# Sheet1.net
KiCad netlist of a schematic drawn in Altium Designer
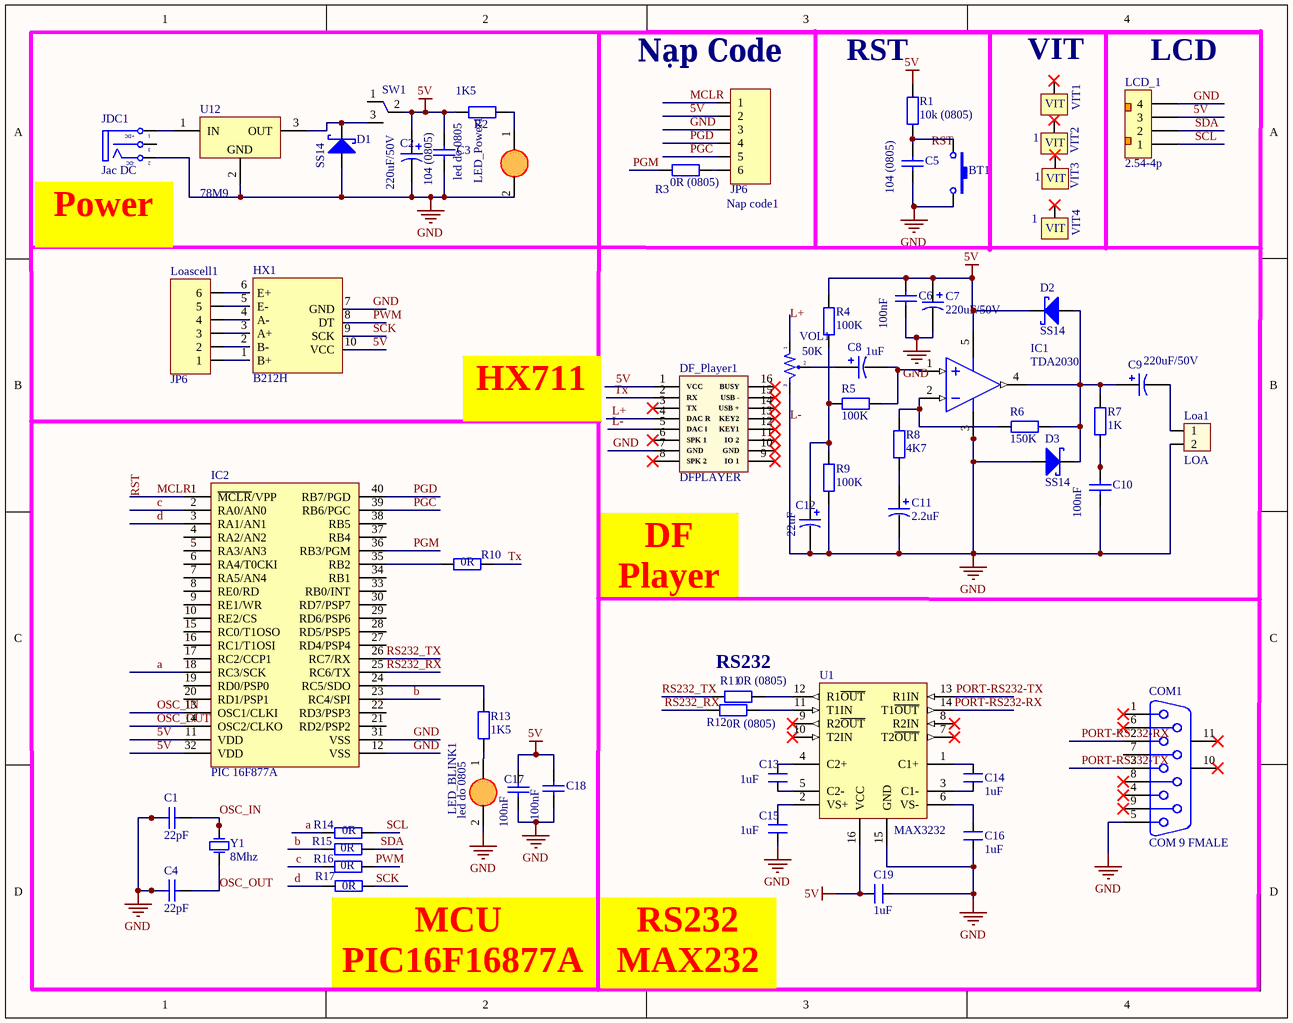
[diagram p0: Sheet1.SchDoc]

(export (version "E")
  (design (tool "Eeschema 10.0.6"))
  (components
    (comp (ref "BT1")
      (value "Nút Nhấn 2 Chân 3x6x2.5MM SMD")
      (footprint "SW2-DIP")
      (description "Dán")
      (libsource (lib "SCH Chuan") (part "Nut Nhan 2 Chan SMD"))
    )
    (comp (ref "C1")
      (value "22pF")
      (footprint "CN1.5")
      (description "Dán")
      (libsource (lib "SCH Chuan") (part "Tu 0805 104 50V 10%"))
    )
    (comp (ref "C2")
      (value "220uF/50V")
      (footprint "CP1.5/3.4")
      (description "CAP ALUM 680uF 20% 16V SMD")
      (fields (field (name "MPN") "EEE-FK1C681P") (field (name "MFR") "Panasonic"))
      (libsource (lib "NhomLib") (part "EEE-FK1C681P"))
    )
    (comp (ref "C3")
      (value "104 (0805)")
      (footprint "CN1.5")
      (description "Dán")
      (libsource (lib "SCH Chuan") (part "Tu 0805 104 50V 10%"))
    )
    (comp (ref "C4")
      (value "22pF")
      (footprint "CN1.5")
      (description "Dán")
      (libsource (lib "SCH Chuan") (part "Tu 0805 104 50V 10%"))
    )
    (comp (ref "C5")
      (value "104 (0805)")
      (footprint "CN1.5")
      (description "Dán")
      (libsource (lib "SCH Chuan") (part "Tu 0805 104 50V 10%"))
    )
    (comp (ref "C6")
      (value "100nF")
      (footprint "CN1.5")
      (description "Dán")
      (libsource (lib "SCH Chuan") (part "Tu 0805 104 50V 10%"))
    )
    (comp (ref "C7")
      (value "220uF/50V")
      (footprint "CP1.5/3.4")
      (description "CAP ALUM 680uF 20% 16V SMD")
      (fields (field (name "MPN") "EEE-FK1C681P") (field (name "MFR") "Panasonic"))
      (libsource (lib "NhomLib") (part "EEE-FK1C681P"))
    )
    (comp (ref "C8")
      (value "1uF")
      (footprint "CP1/2")
      (description "CAP ALUM 47uF 20% 50V SMD")
      (fields (field (name "MPN") "EEE-1HA470XP"))
      (libsource (lib "NhomLib") (part "EEE-1HA470XP"))
    )
    (comp (ref "C9")
      (value "220uF/50V")
      (footprint "CP1.5/3.4")
      (description "CAP ALUM 680uF 20% 16V SMD")
      (fields (field (name "MPN") "EEE-FK1C681P") (field (name "MFR") "Panasonic"))
      (libsource (lib "NhomLib") (part "EEE-FK1C681P"))
    )
    (comp (ref "C10")
      (value "100nF")
      (footprint "CN1.5")
      (description "Dán")
      (libsource (lib "SCH Chuan") (part "Tu 0805 104 50V 10%"))
    )
    (comp (ref "C11")
      (value "2.2uF")
      (footprint "CP1/2")
      (description "CAP ALUM 47uF 20% 50V SMD")
      (fields (field (name "MPN") "EEE-1HA470XP"))
      (libsource (lib "NhomLib") (part "EEE-1HA470XP"))
    )
    (comp (ref "C12")
      (value "22uF")
      (footprint "CP1/2")
      (description "CAP ALUM 47uF 20% 50V SMD")
      (fields (field (name "MPN") "EEE-1HA470XP"))
      (libsource (lib "NhomLib") (part "EEE-1HA470XP"))
    )
    (comp (ref "C13")
      (value "1uF")
      (footprint "CN1.5")
      (description "CAP CER 0.1UF 50V X7R 0805")
      (fields
        (field (name "MANUFACTURER") "AVX Corporation")
        (field (name "MANUFACTURER PART NUMBER") "08055C104KAT2A")
      )
      (libsource (lib "Tran Tuan") (part "CAP-CER/100nF/50V/X7R/0805"))
    )
    (comp (ref "C14")
      (value "1uF")
      (footprint "CN1.5")
      (description "CAP CER 0.1UF 50V X7R 0805")
      (fields
        (field (name "MANUFACTURER") "AVX Corporation")
        (field (name "MANUFACTURER PART NUMBER") "08055C104KAT2A")
      )
      (libsource (lib "Tran Tuan") (part "CAP-CER/100nF/50V/X7R/0805"))
    )
    (comp (ref "C15")
      (value "1uF")
      (footprint "CN1.5")
      (description "CAP CER 0.1UF 50V X7R 0805")
      (fields
        (field (name "MANUFACTURER") "AVX Corporation")
        (field (name "MANUFACTURER PART NUMBER") "08055C104KAT2A")
      )
      (libsource (lib "Tran Tuan") (part "CAP-CER/100nF/50V/X7R/0805"))
    )
    (comp (ref "C16")
      (value "1uF")
      (footprint "CN1.5")
      (description "CAP CER 0.1UF 50V X7R 0805")
      (fields
        (field (name "MANUFACTURER") "AVX Corporation")
        (field (name "MANUFACTURER PART NUMBER") "08055C104KAT2A")
      )
      (libsource (lib "Tran Tuan") (part "CAP-CER/100nF/50V/X7R/0805"))
    )
    (comp (ref "C17")
      (value "100nF")
      (footprint "CN1.5")
      (description "Dán")
      (libsource (lib "SCH Chuan") (part "Tu 0805 104 50V 10%"))
    )
    (comp (ref "C18")
      (value "100nF")
      (footprint "CN1.5")
      (description "Dán")
      (libsource (lib "SCH Chuan") (part "Tu 0805 104 50V 10%"))
    )
    (comp (ref "C19")
      (value "1uF")
      (footprint "CN1.5")
      (description "CAP CER 0.1UF 50V X7R 0805")
      (fields
        (field (name "MANUFACTURER") "AVX Corporation")
        (field (name "MANUFACTURER PART NUMBER") "08055C104KAT2A")
      )
      (libsource (lib "Tran Tuan") (part "CAP-CER/100nF/50V/X7R/0805"))
    )
    (comp (ref "COM1")
      (value "COM 9 FMALE")
      (footprint "DSB 9-F")
      (description "COM 9")
      (fields (field (name "PUBLISHER") "Altium Limited"))
      (libsource (lib "syhaunguyen") (part "DSB9F"))
    )
    (comp (ref "D1")
      (value "SS14")
      (footprint "DIO-1A")
      (description "Dán")
      (libsource (lib "SCH Chuan") (part "Diode SS14 ( 1N5819)"))
    )
    (comp (ref "D2")
      (value "SS14")
      (footprint "DIO-1A")
      (description "Dán")
      (libsource (lib "SCH Chuan") (part "Diode SS14 ( 1N5819)"))
    )
    (comp (ref "D3")
      (value "SS14")
      (footprint "DIO-1A")
      (description "Dán")
      (libsource (lib "SCH Chuan") (part "Diode SS14 ( 1N5819)"))
    )
    (comp (ref "DF_Player1")
      (value "DFPLAYER")
      (footprint "DFPLAYER")
      (libsource (lib "VanThoLIB") (part "DFPLAYER"))
    )
    (comp (ref "HX1")
      (value "B212H")
      (footprint "Module_HX711")
      (description "Module_HX711")
      (libsource (lib "VanThoLIB") (part "Module_HX711"))
    )
    (comp (ref "IC1")
      (value "TDA2030")
      (footprint "DIP5SL1")
      (description "14W Hi-Fi AUDIO AMPLIFIER")
      (libsource (lib "syhaunguyen") (part "TDA2030"))
    )
    (comp (ref "IC2")
      (value "PIC 16F877A")
      (footprint "DIP40/W0.6")
      (description "8K FLASH, 368B RAM, 256B EFROM")
      (fields (field (name "COPYRIGHT BY") "VanDungEvn"))
      (libsource (lib "LIBRARY") (part "PIC16F877-PU"))
    )
    (comp (ref "JDC1")
      (value "Jac DC")
      (footprint "DC-IN")
      (description "Jac DC input")
      (libsource (lib "NhomLib") (part "DCIN"))
    )
    (comp (ref "LCD_1")
      (value "2.54-4p")
      (footprint "Header Duc Thang 4p 2.54")
      (description "Cắm")
      (libsource (lib "B212H") (part "Header 2.54_4p Duc Thang"))
    )
    (comp (ref "LED_BLINK1")
      (value "led do 0805")
      (footprint "LED-5-Green")
      (description "Dán")
      (libsource (lib "SCH Chuan") (part "Led 0805 Do"))
    )
    (comp (ref "LED_Power1")
      (value "led do 0805")
      (footprint "LED-5-Green")
      (description "Dán")
      (libsource (lib "SCH Chuan") (part "Led 0805 Do"))
    )
    (comp (ref "Loa1")
      (value "LOA")
      (footprint "CON2")
      (description "Header 2.54mm Through Hole")
      (fields
        (field (name "MANUFACTURER") "TE Connectivity AMP Connectors")
        (field (name "MANUFACTURER PART NUMBER") "640456-2")
      )
      (libsource (lib "LPSON") (part "Header 2 2.54mm"))
    )
    (comp (ref "Loascell1")
      (value "JP6")
      (footprint "HDR6")
      (description "WR-PHD 2.54 mm Angled Socket Header")
      (fields
        (field (name "MANUFACTURER") "Würth Elektronik eiSos GmbH")
        (field (name "PARTNO") "613006143121")
        (field (name "CREATED BY") "Karrer Zheng")
      )
      (libsource (lib "LIBRARY") (part "JP6"))
    )
    (comp (ref "Nap code1")
      (value "JP6")
      (footprint "JP6-D1T")
      (description "WR-PHD 2.54 mm Angled Socket Header")
      (fields
        (field (name "MANUFACTURER") "Würth Elektronik eiSos GmbH")
        (field (name "PARTNO") "613006143121")
        (field (name "CREATED BY") "Karrer Zheng")
      )
      (libsource (lib "") (part "JP6_1"))
    )
    (comp (ref "R1")
      (value "10k (0805)")
      (footprint "RES-1/4W")
      (description "Dán")
      (libsource (lib "SCH Chuan") (part "Tro 0805 5% 10k"))
    )
    (comp (ref "R2")
      (value "1K5")
      (footprint "RES-1/4W")
      (description "Dán")
      (libsource (lib "SCH Chuan") (part "Tro 0805 5% 470R"))
    )
    (comp (ref "R3")
      (value "0R (0805)")
      (footprint "RES-1/4W")
      (description "Dán")
      (libsource (lib "SCH Chuan") (part "Tro 0805 5% 470R"))
    )
    (comp (ref "R4")
      (value "100K")
      (footprint "RES-1/4W")
      (description "Dán")
      (libsource (lib "SCH Chuan") (part "Tro 0805 5% 10k"))
    )
    (comp (ref "R5")
      (value "100K")
      (footprint "RES-1/4W")
      (description "Dán")
      (libsource (lib "SCH Chuan") (part "Tro 0805 5% 10k"))
    )
    (comp (ref "R6")
      (value "150K")
      (footprint "RES-1/4W")
      (description "Dán")
      (libsource (lib "SCH Chuan") (part "Tro 0805 5% 10k"))
    )
    (comp (ref "R7")
      (value "1K")
      (footprint "RES-1/4W")
      (description "Dán")
      (libsource (lib "SCH Chuan") (part "Tro 0805 5% 10k"))
    )
    (comp (ref "R8")
      (value "4K7")
      (footprint "RES-1/4W")
      (description "Dán")
      (libsource (lib "SCH Chuan") (part "Tro 0805 5% 10k"))
    )
    (comp (ref "R9")
      (value "100K")
      (footprint "RES-1/4W")
      (description "Dán")
      (libsource (lib "SCH Chuan") (part "Tro 0805 5% 10k"))
    )
    (comp (ref "R10")
      (value "0R")
      (footprint "RES-1/4W")
      (description "Dán")
      (libsource (lib "SCH Chuan") (part "Tro 0805 5% 470R"))
    )
    (comp (ref "R11")
      (value "0R (0805)")
      (footprint "RES-1/4W")
      (description "Dán")
      (libsource (lib "SCH Chuan") (part "Tro 0805 5% 470R"))
    )
    (comp (ref "R12")
      (value "0R (0805)")
      (footprint "RES-1/4W")
      (description "Dán")
      (libsource (lib "SCH Chuan") (part "Tro 0805 5% 470R"))
    )
    (comp (ref "R13")
      (value "1K5")
      (footprint "RES-1/4W")
      (description "Dán")
      (libsource (lib "SCH Chuan") (part "Tro 0805 5% 470R"))
    )
    (comp (ref "R14")
      (value "0R")
      (footprint "RES-1/4W")
      (description "Dán")
      (libsource (lib "SCH Chuan") (part "Tro 0805 5% 470R"))
    )
    (comp (ref "R15")
      (value "0R")
      (footprint "RES-1/4W")
      (description "Dán")
      (libsource (lib "SCH Chuan") (part "Tro 0805 5% 470R"))
    )
    (comp (ref "R16")
      (value "0R")
      (footprint "RES-1/4W")
      (description "Dán")
      (libsource (lib "SCH Chuan") (part "Tro 0805 5% 470R"))
    )
    (comp (ref "R17")
      (value "0R")
      (footprint "RES-1/4W")
      (description "Dán")
      (libsource (lib "SCH Chuan") (part "Tro 0805 5% 470R"))
    )
    (comp (ref "SW1") (value "Switch") (footprint "JP3-C1T") (libsource (lib "VanThoLIB") (part "Switch")))
    (comp (ref "U1")
      (value "MAX3232")
      (footprint "DIP16")
      (description "RS232 LEVEL SHIFTER")
      (fields
        (field (name "MANUFACTURER PART NUMBER") "MAX232DR")
        (field (name "MANUFACTURER") "Texas Instruments")
      )
      (libsource (lib "LIBRARY") (part "MAX232"))
    )
    (comp (ref "U12")
      (value "78M9")
      (footprint "HDR1x3 BIG")
      (description "Dán")
      (libsource (lib "NhomLib") (part "7809"))
    )
    (comp (ref "VIT1")
      (value "1")
      (footprint "VIT")
      (description "Oc Vit")
      (libsource (lib "syhaunguyen") (part "VIT"))
    )
    (comp (ref "VIT2")
      (value "1")
      (footprint "VIT")
      (description "Oc Vit")
      (libsource (lib "syhaunguyen") (part "VIT"))
    )
    (comp (ref "VIT3")
      (value "1")
      (footprint "VIT")
      (description "Oc Vit")
      (libsource (lib "syhaunguyen") (part "VIT"))
    )
    (comp (ref "VIT4")
      (value "1")
      (footprint "VIT")
      (description "Oc Vit")
      (libsource (lib "syhaunguyen") (part "VIT"))
    )
    (comp (ref "VOL1")
      (value "50K")
      (footprint "VOL-D")
      (description "Var Resistor")
      (libsource (lib "syhaunguyen") (part "VOL-S"))
    )
    (comp (ref "Y1")
      (value "8Mhz")
      (footprint "THACH ANH CAM")
      (description "Dán")
      (libsource (lib "B212H") (part "Thach Anh 7.3728Mhz 49s SMD"))
    )
  )
  (nets
    (net (code "1") (name "/L+") (class "Default")
      (node (ref "DF_Player1") (pin "4") (pinfunction "DAC_R_4") (pintype "passive"))
      (node (ref "VOL1") (pin "1") (pinfunction "1_1") (pintype "passive"))
    )
    (net (code "2") (name "/MCLR") (class "Default")
      (node (ref "IC2") (pin "1") (pinfunction "~{MCLR}/VPP_1") (pintype "passive"))
      (node (ref "Nap code1") (pin "1") (pinfunction "1_1") (pintype "passive"))
    )
    (net (code "3") (name "/OSC_IN") (class "Default")
      (node (ref "C1") (pin "1") (pinfunction "1_1") (pintype "passive"))
      (node (ref "IC2") (pin "13") (pinfunction "OSC1/CLKI_13") (pintype "passive"))
      (node (ref "Y1") (pin "1") (pinfunction "OSC1_1") (pintype "passive"))
    )
    (net (code "4") (name "/OSC_OUT") (class "Default")
      (node (ref "C4") (pin "1") (pinfunction "1_1") (pintype "passive"))
      (node (ref "IC2") (pin "14") (pinfunction "OSC2/CLKO_14") (pintype "passive"))
      (node (ref "Y1") (pin "2") (pinfunction "OSC2_2") (pintype "passive"))
    )
    (net (code "5") (name "/PGC") (class "Default")
      (node (ref "IC2") (pin "39") (pinfunction "RB6/PGC_39") (pintype "passive"))
      (node (ref "Nap code1") (pin "5") (pinfunction "5_5") (pintype "passive"))
    )
    (net (code "6") (name "/PGD") (class "Default")
      (node (ref "IC2") (pin "40") (pinfunction "RB7/PGD_40") (pintype "passive"))
      (node (ref "Nap code1") (pin "4") (pinfunction "4_4") (pintype "passive"))
    )
    (net (code "7") (name "/PGM") (class "Default")
      (node (ref "IC2") (pin "36") (pinfunction "RB3/PGM_36") (pintype "passive"))
      (node (ref "R3") (pin "1") (pinfunction "1_1") (pintype "passive"))
    )
    (net (code "8") (name "/PORT-RS232-RX") (class "Default")
      (node (ref "COM1") (pin "2") (pinfunction "2_2") (pintype "passive"))
      (node (ref "U1") (pin "14") (pinfunction "T1~{OUT}_14") (pintype "output"))
    )
    (net (code "9") (name "/PORT-RS232-TX") (class "Default")
      (node (ref "COM1") (pin "3") (pinfunction "3_3") (pintype "passive"))
      (node (ref "U1") (pin "13") (pinfunction "R1IN_13") (pintype "input"))
    )
    (net (code "10") (name "/PWM") (class "Default")
      (node (ref "HX1") (pin "8") (pinfunction "DT_8") (pintype "input"))
      (node (ref "R16") (pin "2") (pinfunction "2_2") (pintype "passive"))
    )
    (net (code "11") (name "/RS232_RX") (class "Default")
      (node (ref "IC2") (pin "25") (pinfunction "RC6/TX_25") (pintype "passive"))
      (node (ref "R12") (pin "1") (pinfunction "1_1") (pintype "passive"))
    )
    (net (code "12") (name "/RS232_TX") (class "Default")
      (node (ref "IC2") (pin "26") (pinfunction "RC7/RX_26") (pintype "passive"))
      (node (ref "R11") (pin "1") (pinfunction "1_1") (pintype "passive"))
    )
    (net (code "13") (name "/SCK") (class "Default")
      (node (ref "HX1") (pin "9") (pinfunction "SCK_9") (pintype "input"))
      (node (ref "R17") (pin "1") (pinfunction "1_1") (pintype "passive"))
    )
    (net (code "14") (name "/SCL") (class "Default")
      (node (ref "LCD_1") (pin "1") (pinfunction "1_1") (pintype "passive"))
      (node (ref "R14") (pin "2") (pinfunction "2_2") (pintype "passive"))
    )
    (net (code "15") (name "/SDA") (class "Default")
      (node (ref "LCD_1") (pin "2") (pinfunction "2_2") (pintype "passive"))
      (node (ref "R15") (pin "2") (pinfunction "2_2") (pintype "passive"))
    )
    (net (code "16") (name "/Tx") (class "Default")
      (node (ref "DF_Player1") (pin "2") (pinfunction "RX_2") (pintype "passive"))
      (node (ref "R10") (pin "2") (pinfunction "2_2") (pintype "passive"))
    )
    (net (code "17") (name "/a") (class "Default")
      (node (ref "IC2") (pin "18") (pinfunction "RC3/SCK_18") (pintype "passive"))
      (node (ref "R14") (pin "1") (pinfunction "1_1") (pintype "passive"))
    )
    (net (code "18") (name "/b") (class "Default")
      (node (ref "IC2") (pin "23") (pinfunction "RC4/SPI_23") (pintype "passive"))
      (node (ref "R15") (pin "1") (pinfunction "1_1") (pintype "passive"))
    )
    (net (code "19") (name "/c") (class "Default")
      (node (ref "IC2") (pin "2") (pinfunction "RA0/AN0_2") (pintype "passive"))
      (node (ref "R16") (pin "1") (pinfunction "1_1") (pintype "passive"))
    )
    (net (code "20") (name "/d") (class "Default")
      (node (ref "IC2") (pin "3") (pinfunction "RA1/AN1_3") (pintype "passive"))
      (node (ref "R17") (pin "2") (pinfunction "2_2") (pintype "passive"))
    )
    (net (code "21") (name "5V") (class "Default")
      (node (ref "C17") (pin "1") (pinfunction "1_1") (pintype "passive"))
      (node (ref "C18") (pin "1") (pinfunction "1_1") (pintype "passive"))
      (node (ref "C19") (pin "1") (pinfunction "1_1") (pintype "passive"))
      (node (ref "C2") (pin "1") (pinfunction "1_1") (pintype "passive"))
      (node (ref "C3") (pin "1") (pinfunction "1_1") (pintype "passive"))
      (node (ref "C6") (pin "1") (pinfunction "1_1") (pintype "passive"))
      (node (ref "C7") (pin "1") (pinfunction "1_1") (pintype "passive"))
      (node (ref "D2") (pin "2") (pinfunction "K_2") (pintype "passive"))
      (node (ref "DF_Player1") (pin "1") (pinfunction "VCC_1") (pintype "power_in"))
      (node (ref "HX1") (pin "10") (pinfunction "VCC_10") (pintype "input"))
      (node (ref "IC1") (pin "5") (pinfunction "V+_5") (pintype "power_in"))
      (node (ref "IC2") (pin "11") (pinfunction "VDD_11") (pintype "passive"))
      (node (ref "IC2") (pin "32") (pinfunction "VDD_32") (pintype "passive"))
      (node (ref "LCD_1") (pin "3") (pinfunction "3_3") (pintype "passive"))
      (node (ref "Nap code1") (pin "2") (pinfunction "2_2") (pintype "passive"))
      (node (ref "R1") (pin "2") (pinfunction "2_2") (pintype "passive"))
      (node (ref "R2") (pin "1") (pinfunction "1_1") (pintype "passive"))
      (node (ref "R4") (pin "1") (pinfunction "1_1") (pintype "passive"))
      (node (ref "SW1") (pin "2") (pinfunction "1_2") (pintype "passive"))
      (node (ref "U1") (pin "16") (pinfunction "VCC_16") (pintype "power_in"))
    )
    (net (code "22") (name "GND") (class "Default")
      (node (ref "BT1") (pin "2") (pinfunction "2_2") (pintype "passive"))
      (node (ref "C1") (pin "2") (pinfunction "2_2") (pintype "passive"))
      (node (ref "C10") (pin "2") (pinfunction "2_2") (pintype "passive"))
      (node (ref "C11") (pin "2") (pinfunction "2_2") (pintype "passive"))
      (node (ref "C12") (pin "2") (pinfunction "2_2") (pintype "passive"))
      (node (ref "C15") (pin "2") (pinfunction "2_2") (pintype "passive"))
      (node (ref "C16") (pin "2") (pinfunction "2_2") (pintype "passive"))
      (node (ref "C17") (pin "2") (pinfunction "2_2") (pintype "passive"))
      (node (ref "C18") (pin "2") (pinfunction "2_2") (pintype "passive"))
      (node (ref "C19") (pin "2") (pinfunction "2_2") (pintype "passive"))
      (node (ref "C2") (pin "2") (pinfunction "2_2") (pintype "passive"))
      (node (ref "C3") (pin "2") (pinfunction "2_2") (pintype "passive"))
      (node (ref "C4") (pin "2") (pinfunction "2_2") (pintype "passive"))
      (node (ref "C5") (pin "2") (pinfunction "2_2") (pintype "passive"))
      (node (ref "C6") (pin "2") (pinfunction "2_2") (pintype "passive"))
      (node (ref "C7") (pin "2") (pinfunction "2_2") (pintype "passive"))
      (node (ref "COM1") (pin "5") (pinfunction "5_5") (pintype "passive"))
      (node (ref "D1") (pin "1") (pinfunction "A_1") (pintype "passive"))
      (node (ref "D3") (pin "1") (pinfunction "A_1") (pintype "passive"))
      (node (ref "DF_Player1") (pin "5") (pinfunction "DAC_l_5") (pintype "passive"))
      (node (ref "DF_Player1") (pin "7") (pinfunction "GND_7") (pintype "power_in"))
      (node (ref "HX1") (pin "7") (pinfunction "GND_7") (pintype "input"))
      (node (ref "IC1") (pin "3") (pinfunction "V-_3") (pintype "power_in"))
      (node (ref "IC2") (pin "12") (pinfunction "VSS_12") (pintype "passive"))
      (node (ref "IC2") (pin "31") (pinfunction "VSS_31") (pintype "passive"))
      (node (ref "JDC1") (pin "2") (pinfunction "TN_2") (pintype "passive"))
      (node (ref "LCD_1") (pin "4") (pinfunction "4_4") (pintype "passive"))
      (node (ref "LED_BLINK1") (pin "2") (pinfunction "K_2") (pintype "passive"))
      (node (ref "LED_Power1") (pin "2") (pinfunction "K_2") (pintype "passive"))
      (node (ref "Loa1") (pin "2") (pinfunction "2_2") (pintype "passive"))
      (node (ref "Nap code1") (pin "3") (pinfunction "3_3") (pintype "passive"))
      (node (ref "R9") (pin "2") (pinfunction "2_2") (pintype "passive"))
      (node (ref "U1") (pin "15") (pinfunction "GND_15") (pintype "power_in"))
      (node (ref "U12") (pin "2") (pinfunction "GND_2") (pintype "power_in"))
      (node (ref "VOL1") (pin "3") (pinfunction "3_3") (pintype "passive"))
    )
    (net (code "23") (name "Net-(BT1-Pad1)") (class "Default")
      (node (ref "BT1") (pin "1") (pinfunction "1_1") (pintype "passive"))
      (node (ref "C5") (pin "1") (pinfunction "1_1") (pintype "passive"))
      (node (ref "R1") (pin "1") (pinfunction "1_1") (pintype "passive"))
    )
    (net (code "24") (name "Net-(C8-Pad1)") (class "Default")
      (node (ref "C8") (pin "1") (pinfunction "1_1") (pintype "passive"))
      (node (ref "VOL1") (pin "2") (pinfunction "2_2") (pintype "passive"))
    )
    (net (code "25") (name "Net-(C9-Pad2)") (class "Default")
      (node (ref "C9") (pin "2") (pinfunction "2_2") (pintype "passive"))
      (node (ref "Loa1") (pin "1") (pinfunction "1_1") (pintype "passive"))
    )
    (net (code "26") (name "Net-(C10-Pad1)") (class "Default")
      (node (ref "C10") (pin "1") (pinfunction "1_1") (pintype "passive"))
      (node (ref "R7") (pin "2") (pinfunction "2_2") (pintype "passive"))
    )
    (net (code "27") (name "Net-(C11-Pad1)") (class "Default")
      (node (ref "C11") (pin "1") (pinfunction "1_1") (pintype "passive"))
      (node (ref "R8") (pin "2") (pinfunction "2_2") (pintype "passive"))
    )
    (net (code "28") (name "Net-(C12-Pad1)") (class "Default")
      (node (ref "C12") (pin "1") (pinfunction "1_1") (pintype "passive"))
      (node (ref "R4") (pin "2") (pinfunction "2_2") (pintype "passive"))
      (node (ref "R5") (pin "2") (pinfunction "2_2") (pintype "passive"))
      (node (ref "R9") (pin "1") (pinfunction "1_1") (pintype "passive"))
    )
    (net (code "29") (name "Net-(D1-K)") (class "Default")
      (node (ref "D1") (pin "2") (pinfunction "K_2") (pintype "passive"))
      (node (ref "SW1") (pin "3") (pinfunction "1_3") (pintype "passive"))
      (node (ref "U12") (pin "3") (pinfunction "OUT_3") (pintype "power_in"))
    )
    (net (code "30") (name "Net-(D2-A)") (class "Default")
      (node (ref "C9") (pin "1") (pinfunction "1_1") (pintype "passive"))
      (node (ref "D2") (pin "1") (pinfunction "A_1") (pintype "passive"))
      (node (ref "D3") (pin "2") (pinfunction "K_2") (pintype "passive"))
      (node (ref "IC1") (pin "4") (pinfunction "OUT_4") (pintype "output"))
      (node (ref "R6") (pin "1") (pinfunction "1_1") (pintype "passive"))
      (node (ref "R7") (pin "1") (pinfunction "1_1") (pintype "passive"))
    )
    (net (code "31") (name "Net-(HX1-A+)") (class "Default")
      (node (ref "HX1") (pin "3") (pinfunction "A+_3") (pintype "input"))
      (node (ref "Loascell1") (pin "3") (pinfunction "3_3") (pintype "passive"))
    )
    (net (code "32") (name "Net-(HX1-A-)") (class "Default")
      (node (ref "HX1") (pin "4") (pinfunction "A-_4") (pintype "input"))
      (node (ref "Loascell1") (pin "4") (pinfunction "4_4") (pintype "passive"))
    )
    (net (code "33") (name "Net-(HX1-B+)") (class "Default")
      (node (ref "HX1") (pin "1") (pinfunction "B+_1") (pintype "input"))
      (node (ref "Loascell1") (pin "1") (pinfunction "1_1") (pintype "passive"))
    )
    (net (code "34") (name "Net-(HX1-B-)") (class "Default")
      (node (ref "HX1") (pin "2") (pinfunction "B-_2") (pintype "input"))
      (node (ref "Loascell1") (pin "2") (pinfunction "2_2") (pintype "passive"))
    )
    (net (code "35") (name "Net-(HX1-E+)") (class "Default")
      (node (ref "HX1") (pin "6") (pinfunction "E+_6") (pintype "input"))
      (node (ref "Loascell1") (pin "6") (pinfunction "6_6") (pintype "passive"))
    )
    (net (code "36") (name "Net-(HX1-E-)") (class "Default")
      (node (ref "HX1") (pin "5") (pinfunction "E-_5") (pintype "input"))
      (node (ref "Loascell1") (pin "5") (pinfunction "5_5") (pintype "passive"))
    )
    (net (code "37") (name "Net-(IC1-IN+)") (class "Default")
      (node (ref "C8") (pin "2") (pinfunction "2_2") (pintype "passive"))
      (node (ref "IC1") (pin "1") (pinfunction "IN+_1") (pintype "input"))
      (node (ref "R5") (pin "1") (pinfunction "1_1") (pintype "passive"))
    )
    (net (code "38") (name "Net-(IC1-IN-)") (class "Default")
      (node (ref "IC1") (pin "2") (pinfunction "IN-_2") (pintype "input"))
      (node (ref "R6") (pin "2") (pinfunction "2_2") (pintype "passive"))
      (node (ref "R8") (pin "1") (pinfunction "1_1") (pintype "passive"))
    )
    (net (code "39") (name "Net-(IC2-RB2)") (class "Default")
      (node (ref "IC2") (pin "35") (pinfunction "RB2_35") (pintype "passive"))
      (node (ref "R10") (pin "1") (pinfunction "1_1") (pintype "passive"))
    )
    (net (code "40") (name "Net-(IC2-RC5{slash}SDO)") (class "Default")
      (node (ref "IC2") (pin "24") (pinfunction "RC5/SDO_24") (pintype "passive"))
      (node (ref "R13") (pin "2") (pinfunction "2_2") (pintype "passive"))
    )
    (net (code "41") (name "Net-(JDC1-T)") (class "Default")
      (node (ref "JDC1") (pin "1") (pinfunction "T_1") (pintype "passive"))
      (node (ref "U12") (pin "1") (pinfunction "IN_1") (pintype "power_in"))
    )
    (net (code "42") (name "Net-(LED_BLINK1-A)") (class "Default")
      (node (ref "LED_BLINK1") (pin "1") (pinfunction "A_1") (pintype "passive"))
      (node (ref "R13") (pin "1") (pinfunction "1_1") (pintype "passive"))
    )
    (net (code "43") (name "Net-(LED_Power1-A)") (class "Default")
      (node (ref "LED_Power1") (pin "1") (pinfunction "A_1") (pintype "passive"))
      (node (ref "R2") (pin "2") (pinfunction "2_2") (pintype "passive"))
    )
    (net (code "44") (name "Net-(Nap code1-Pad6)") (class "Default")
      (node (ref "Nap code1") (pin "6") (pinfunction "6_6") (pintype "passive"))
      (node (ref "R3") (pin "2") (pinfunction "2_2") (pintype "passive"))
    )
    (net (code "45") (name "Net-(U1-C1+)") (class "Default")
      (node (ref "C14") (pin "1") (pinfunction "1_1") (pintype "passive"))
      (node (ref "U1") (pin "1") (pinfunction "C1+_1") (pintype "passive"))
    )
    (net (code "46") (name "Net-(U1-C1-)") (class "Default")
      (node (ref "C14") (pin "2") (pinfunction "2_2") (pintype "passive"))
      (node (ref "U1") (pin "3") (pinfunction "C1-_3") (pintype "passive"))
    )
    (net (code "47") (name "Net-(U1-C2+)") (class "Default")
      (node (ref "C13") (pin "1") (pinfunction "1_1") (pintype "passive"))
      (node (ref "U1") (pin "4") (pinfunction "C2+_4") (pintype "passive"))
    )
    (net (code "48") (name "Net-(U1-C2-)") (class "Default")
      (node (ref "C13") (pin "2") (pinfunction "2_2") (pintype "passive"))
      (node (ref "U1") (pin "5") (pinfunction "C2-_5") (pintype "passive"))
    )
    (net (code "49") (name "Net-(U1-R1~{OUT})") (class "Default")
      (node (ref "R11") (pin "2") (pinfunction "2_2") (pintype "passive"))
      (node (ref "U1") (pin "12") (pinfunction "R1~{OUT}_12") (pintype "output"))
    )
    (net (code "50") (name "Net-(U1-T1IN)") (class "Default")
      (node (ref "R12") (pin "2") (pinfunction "2_2") (pintype "passive"))
      (node (ref "U1") (pin "11") (pinfunction "T1IN_11") (pintype "input"))
    )
    (net (code "51") (name "Net-(U1-VS+)") (class "Default")
      (node (ref "C15") (pin "1") (pinfunction "1_1") (pintype "passive"))
      (node (ref "U1") (pin "2") (pinfunction "VS+_2") (pintype "power_in"))
    )
    (net (code "52") (name "Net-(U1-VS-)") (class "Default")
      (node (ref "C16") (pin "1") (pinfunction "1_1") (pintype "passive"))
      (node (ref "U1") (pin "6") (pinfunction "VS-_6") (pintype "power_in"))
    )
    (net (code "53") (name "unconnected-(COM1-MH1-Pad10)") (class "Default")
      (node (ref "COM1") (pin "10") (pinfunction "MH1_10") (pintype "passive+no_connect"))
    )
    (net (code "54") (name "unconnected-(COM1-MH2-Pad11)") (class "Default")
      (node (ref "COM1") (pin "11") (pinfunction "MH2_11") (pintype "passive+no_connect"))
    )
    (net (code "55") (name "unconnected-(COM1-Pad1)") (class "Default")
      (node (ref "COM1") (pin "1") (pinfunction "1_1") (pintype "passive+no_connect"))
    )
    (net (code "56") (name "unconnected-(COM1-Pad4)") (class "Default")
      (node (ref "COM1") (pin "4") (pinfunction "4_4") (pintype "passive+no_connect"))
    )
    (net (code "57") (name "unconnected-(COM1-Pad6)") (class "Default")
      (node (ref "COM1") (pin "6") (pinfunction "6_6") (pintype "passive+no_connect"))
    )
    (net (code "58") (name "unconnected-(COM1-Pad7)") (class "Default")
      (node (ref "COM1") (pin "7") (pinfunction "7_7") (pintype "passive"))
    )
    (net (code "59") (name "unconnected-(COM1-Pad8)") (class "Default")
      (node (ref "COM1") (pin "8") (pinfunction "8_8") (pintype "passive+no_connect"))
    )
    (net (code "60") (name "unconnected-(COM1-Pad9)") (class "Default")
      (node (ref "COM1") (pin "9") (pinfunction "9_9") (pintype "passive+no_connect"))
    )
    (net (code "61") (name "unconnected-(DF_Player1-BUSY-Pad16)") (class "Default")
      (node (ref "DF_Player1") (pin "16") (pinfunction "BUSY_16") (pintype "power_in+no_connect"))
    )
    (net (code "62") (name "unconnected-(DF_Player1-GND-Pad10)") (class "Default")
      (node (ref "DF_Player1") (pin "10") (pinfunction "GND_10") (pintype "power_in+no_connect"))
    )
    (net (code "63") (name "unconnected-(DF_Player1-IO_1-Pad9)") (class "Default")
      (node (ref "DF_Player1") (pin "9") (pinfunction "IO_1_9") (pintype "passive+no_connect"))
    )
    (net (code "64") (name "unconnected-(DF_Player1-IO_2-Pad11)") (class "Default")
      (node (ref "DF_Player1") (pin "11") (pinfunction "IO_2_11") (pintype "passive+no_connect"))
    )
    (net (code "65") (name "unconnected-(DF_Player1-KEY1-Pad12)") (class "Default")
      (node (ref "DF_Player1") (pin "12") (pinfunction "KEY1_12") (pintype "passive+no_connect"))
    )
    (net (code "66") (name "unconnected-(DF_Player1-KEY2-Pad13)") (class "Default")
      (node (ref "DF_Player1") (pin "13") (pinfunction "KEY2_13") (pintype "passive+no_connect"))
    )
    (net (code "67") (name "unconnected-(DF_Player1-SPK_1-Pad6)") (class "Default")
      (node (ref "DF_Player1") (pin "6") (pinfunction "SPK_1_6") (pintype "passive+no_connect"))
    )
    (net (code "68") (name "unconnected-(DF_Player1-SPK_2-Pad8)") (class "Default")
      (node (ref "DF_Player1") (pin "8") (pinfunction "SPK_2_8") (pintype "passive+no_connect"))
    )
    (net (code "69") (name "unconnected-(DF_Player1-TX-Pad3)") (class "Default")
      (node (ref "DF_Player1") (pin "3") (pinfunction "TX_3") (pintype "passive+no_connect"))
    )
    (net (code "70") (name "unconnected-(DF_Player1-USB_+-Pad14)") (class "Default")
      (node (ref "DF_Player1") (pin "14") (pinfunction "USB_+_14") (pintype "passive+no_connect"))
    )
    (net (code "71") (name "unconnected-(DF_Player1-USB_--Pad15)") (class "Default")
      (node (ref "DF_Player1") (pin "15") (pinfunction "USB_-_15") (pintype "passive+no_connect"))
    )
    (net (code "72") (name "unconnected-(IC2-RA2{slash}AN2-Pad4)") (class "Default")
      (node (ref "IC2") (pin "4") (pinfunction "RA2/AN2_4") (pintype "passive"))
    )
    (net (code "73") (name "unconnected-(IC2-RA3{slash}AN3-Pad5)") (class "Default")
      (node (ref "IC2") (pin "5") (pinfunction "RA3/AN3_5") (pintype "passive"))
    )
    (net (code "74") (name "unconnected-(IC2-RA4{slash}T0CKI-Pad6)") (class "Default")
      (node (ref "IC2") (pin "6") (pinfunction "RA4/T0CKI_6") (pintype "passive"))
    )
    (net (code "75") (name "unconnected-(IC2-RA5{slash}AN4-Pad7)") (class "Default")
      (node (ref "IC2") (pin "7") (pinfunction "RA5/AN4_7") (pintype "passive"))
    )
    (net (code "76") (name "unconnected-(IC2-RB0{slash}INT-Pad33)") (class "Default")
      (node (ref "IC2") (pin "33") (pinfunction "RB0/INT_33") (pintype "passive"))
    )
    (net (code "77") (name "unconnected-(IC2-RB1-Pad34)") (class "Default")
      (node (ref "IC2") (pin "34") (pinfunction "RB1_34") (pintype "passive"))
    )
    (net (code "78") (name "unconnected-(IC2-RB4-Pad37)") (class "Default")
      (node (ref "IC2") (pin "37") (pinfunction "RB4_37") (pintype "passive"))
    )
    (net (code "79") (name "unconnected-(IC2-RB5-Pad38)") (class "Default")
      (node (ref "IC2") (pin "38") (pinfunction "RB5_38") (pintype "passive"))
    )
    (net (code "80") (name "unconnected-(IC2-RC0{slash}T1OSO-Pad15)") (class "Default")
      (node (ref "IC2") (pin "15") (pinfunction "RC0/T1OSO_15") (pintype "passive"))
    )
    (net (code "81") (name "unconnected-(IC2-RC1{slash}T1OSI-Pad16)") (class "Default")
      (node (ref "IC2") (pin "16") (pinfunction "RC1/T1OSI_16") (pintype "passive"))
    )
    (net (code "82") (name "unconnected-(IC2-RC2{slash}CCP1-Pad17)") (class "Default")
      (node (ref "IC2") (pin "17") (pinfunction "RC2/CCP1_17") (pintype "passive"))
    )
    (net (code "83") (name "unconnected-(IC2-RD0{slash}PSP0-Pad19)") (class "Default")
      (node (ref "IC2") (pin "19") (pinfunction "RD0/PSP0_19") (pintype "passive"))
    )
    (net (code "84") (name "unconnected-(IC2-RD1{slash}PSP1-Pad20)") (class "Default")
      (node (ref "IC2") (pin "20") (pinfunction "RD1/PSP1_20") (pintype "passive"))
    )
    (net (code "85") (name "unconnected-(IC2-RD2{slash}PSP2-Pad21)") (class "Default")
      (node (ref "IC2") (pin "21") (pinfunction "RD2/PSP2_21") (pintype "passive"))
    )
    (net (code "86") (name "unconnected-(IC2-RD3{slash}PSP3-Pad22)") (class "Default")
      (node (ref "IC2") (pin "22") (pinfunction "RD3/PSP3_22") (pintype "passive"))
    )
    (net (code "87") (name "unconnected-(IC2-RD4{slash}PSP4-Pad27)") (class "Default")
      (node (ref "IC2") (pin "27") (pinfunction "RD4/PSP4_27") (pintype "passive"))
    )
    (net (code "88") (name "unconnected-(IC2-RD5{slash}PSP5-Pad28)") (class "Default")
      (node (ref "IC2") (pin "28") (pinfunction "RD5/PSP5_28") (pintype "passive"))
    )
    (net (code "89") (name "unconnected-(IC2-RD6{slash}PSP6-Pad29)") (class "Default")
      (node (ref "IC2") (pin "29") (pinfunction "RD6/PSP6_29") (pintype "passive"))
    )
    (net (code "90") (name "unconnected-(IC2-RD7{slash}PSP7-Pad30)") (class "Default")
      (node (ref "IC2") (pin "30") (pinfunction "RD7/PSP7_30") (pintype "passive"))
    )
    (net (code "91") (name "unconnected-(IC2-RE0{slash}RD-Pad8)") (class "Default")
      (node (ref "IC2") (pin "8") (pinfunction "RE0/RD_8") (pintype "passive"))
    )
    (net (code "92") (name "unconnected-(IC2-RE1{slash}WR-Pad9)") (class "Default")
      (node (ref "IC2") (pin "9") (pinfunction "RE1/WR_9") (pintype "passive"))
    )
    (net (code "93") (name "unconnected-(IC2-RE2{slash}CS-Pad10)") (class "Default")
      (node (ref "IC2") (pin "10") (pinfunction "RE2/CS_10") (pintype "passive"))
    )
    (net (code "94") (name "unconnected-(JDC1-S-Pad3)") (class "Default")
      (node (ref "JDC1") (pin "3") (pinfunction "S_3") (pintype "power_in"))
    )
    (net (code "95") (name "unconnected-(SW1-Pad1)") (class "Default")
      (node (ref "SW1") (pin "1") (pinfunction "1_1") (pintype "passive"))
    )
    (net (code "96") (name "unconnected-(U1-R2IN-Pad8)") (class "Default")
      (node (ref "U1") (pin "8") (pinfunction "R2IN_8") (pintype "input+no_connect"))
    )
    (net (code "97") (name "unconnected-(U1-R2~{OUT}-Pad9)") (class "Default")
      (node (ref "U1") (pin "9") (pinfunction "R2~{OUT}_9") (pintype "output+no_connect"))
    )
    (net (code "98") (name "unconnected-(U1-T2IN-Pad10)") (class "Default")
      (node (ref "U1") (pin "10") (pinfunction "T2IN_10") (pintype "input+no_connect"))
    )
    (net (code "99") (name "unconnected-(U1-T2~{OUT}-Pad7)") (class "Default")
      (node (ref "U1") (pin "7") (pinfunction "T2~{OUT}_7") (pintype "output+no_connect"))
    )
    (net (code "100") (name "unconnected-(VIT1-1-PadVIT1)") (class "Default")
      (node (ref "VIT1") (pin "VIT1") (pinfunction "1_VIT1") (pintype "passive+no_connect"))
    )
    (net (code "101") (name "unconnected-(VIT2-1-PadVIT1)") (class "Default")
      (node (ref "VIT2") (pin "VIT1") (pinfunction "1_VIT1") (pintype "passive+no_connect"))
    )
    (net (code "102") (name "unconnected-(VIT3-1-PadVIT1)") (class "Default")
      (node (ref "VIT3") (pin "VIT1") (pinfunction "1_VIT1") (pintype "passive+no_connect"))
    )
    (net (code "103") (name "unconnected-(VIT4-1-PadVIT1)") (class "Default")
      (node (ref "VIT4") (pin "VIT1") (pinfunction "1_VIT1") (pintype "passive+no_connect"))
    )
  )
)
